# OpticalProbeTest.net
KiCad netlist of a schematic drawn in Altium Designer
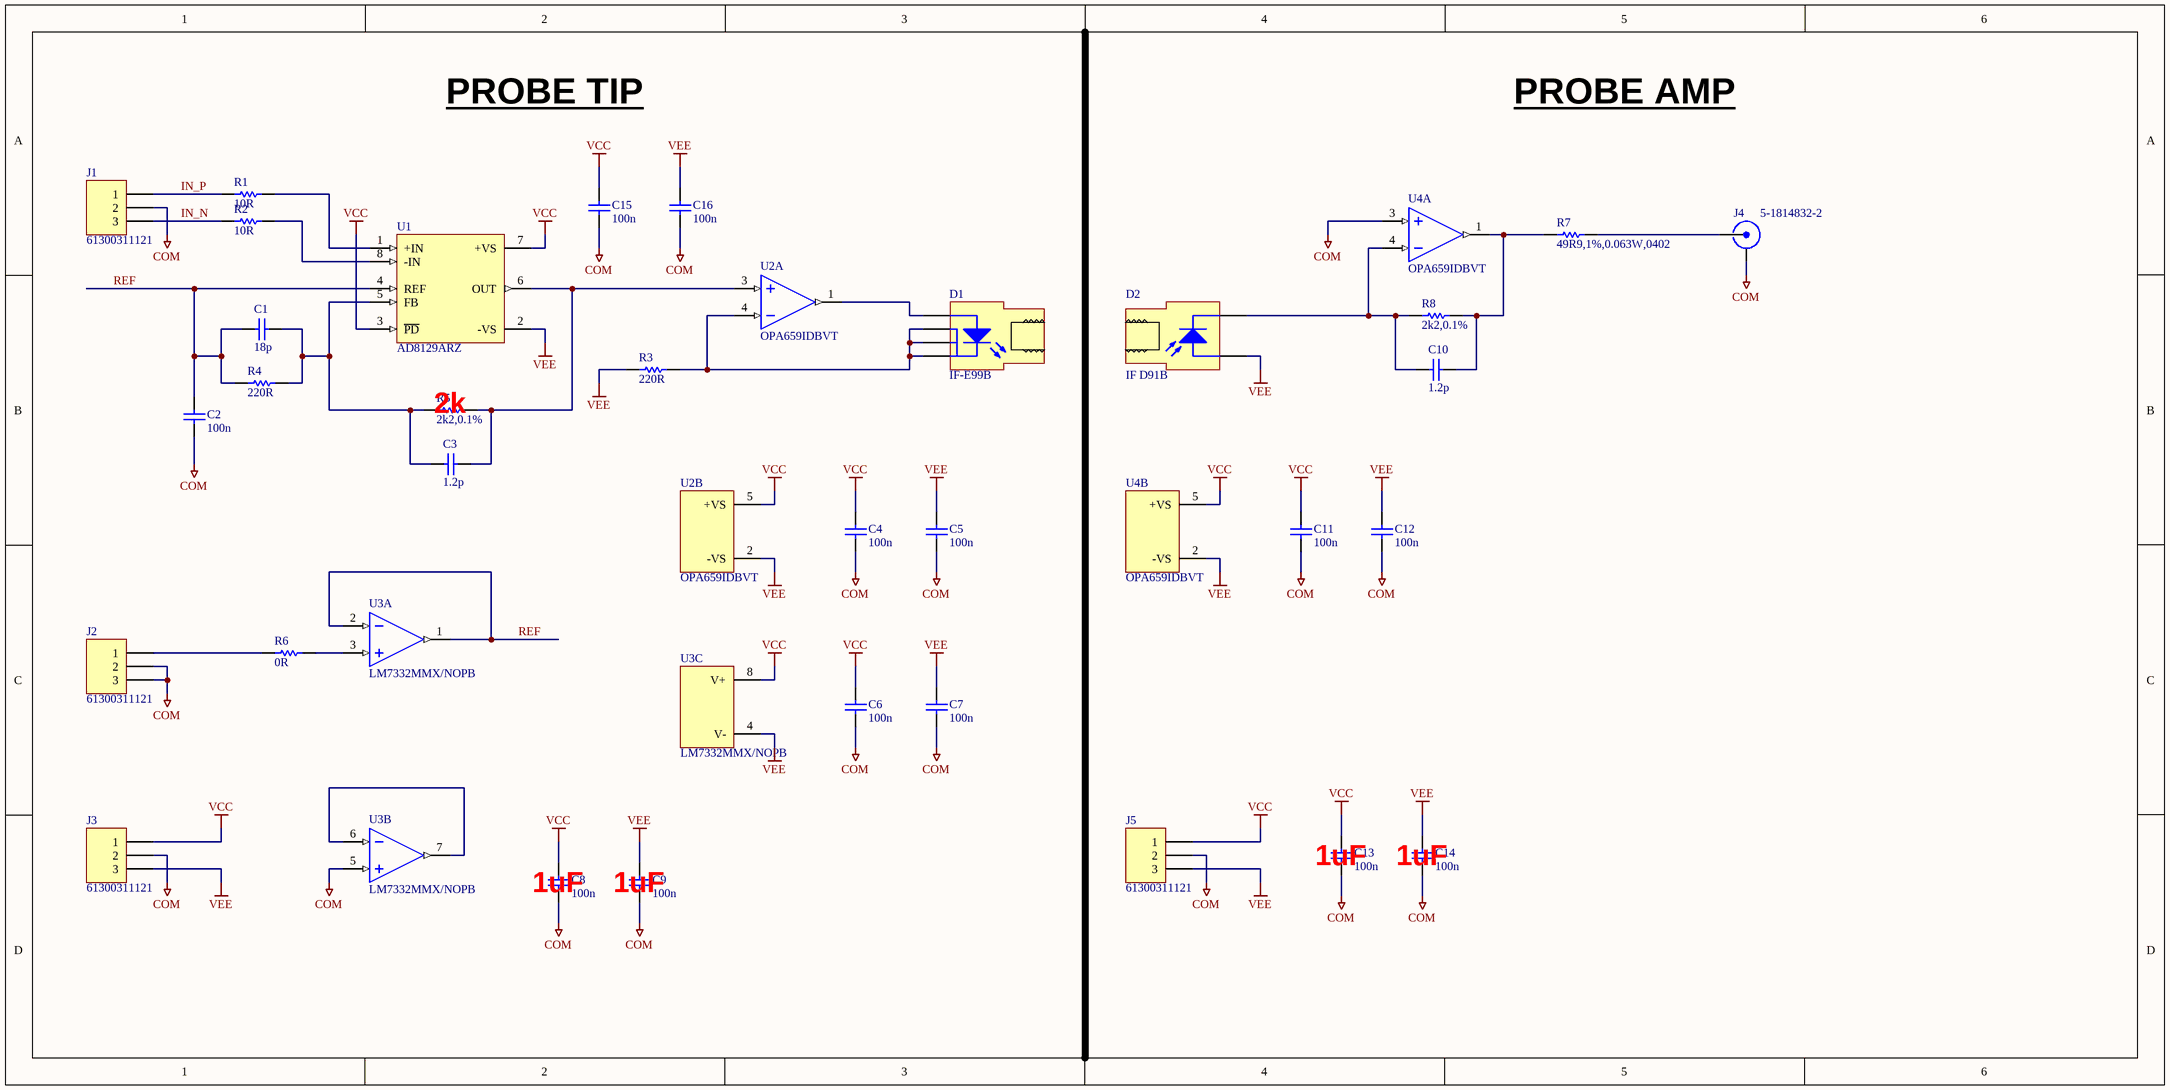
[diagram p0: OpticalProbeTest.SchDoc]

(export (version "E")
  (design (tool "Eeschema 10.0.6"))
  (components
    (comp (ref "C1")
      (value "18p")
      (footprint "CAPC1005X06N")
      (description "18 pF ï¿½5% 25V Ceramic Capacitor C0G, NP0 0402 (1005 Metric)")
      (fields
        (field (name "MANUFACTURER 1 PART NUMBER") "0402N180J250CT")
        (field (name "VENDOR 1 PART NUMBER") "1292-1265-1-ND")
        (field (name "CREATEDBY") "Judd Foster")
      )
      (libsource (lib "Component Library") (part "CAP,Cer,18pF,25VDC,C0G,0402"))
    )
    (comp (ref "C2")
      (value "100n")
      (footprint "CAPC1005X06N")
      (description "0.1ï¿½F ï¿½10% 25V Ceramic Capacitor X7R 0402 (1005 Metric)")
      (fields
        (field (name "MANUFACTURER 1 PART NUMBER") "GRM155R71E104KE14J")
        (field (name "VENDOR 1 PART NUMBER") "490-14603-1-ND")
        (field (name "CREATEDBY") "Judd Foster")
      )
      (libsource (lib "Component Library") (part "CAP,Cer,100nF,25VDC,X7R,0402"))
    )
    (comp (ref "C3")
      (value "1.2p")
      (footprint "CAPC1005X06N")
      (description "1.2 pF ï¿½0.1pF 50V Ceramic Capacitor C0G, NP0 0402 (1005 Metric)")
      (fields
        (field (name "MANUFACTURER 1 PART NUMBER") "GRM1555C1H1R2BA01D")
        (field (name "VENDOR 1 PART NUMBER") "490-6209-1-ND")
        (field (name "CREATEDBY") "Judd Foster")
      )
      (libsource (lib "Component Library") (part "CAP,Cer,1.2pF,50V,C0G,0402"))
    )
    (comp (ref "C4")
      (value "100n")
      (footprint "CAPC1005X06N")
      (description "0.1ï¿½F ï¿½10% 25V Ceramic Capacitor X7R 0402 (1005 Metric)")
      (fields
        (field (name "MANUFACTURER 1 PART NUMBER") "GRM155R71E104KE14J")
        (field (name "VENDOR 1 PART NUMBER") "490-14603-1-ND")
        (field (name "CREATEDBY") "Judd Foster")
      )
      (libsource (lib "Component Library") (part "CAP,Cer,100nF,25VDC,X7R,0402"))
    )
    (comp (ref "C5")
      (value "100n")
      (footprint "CAPC1005X06N")
      (description "0.1ï¿½F ï¿½10% 25V Ceramic Capacitor X7R 0402 (1005 Metric)")
      (fields
        (field (name "MANUFACTURER 1 PART NUMBER") "GRM155R71E104KE14J")
        (field (name "VENDOR 1 PART NUMBER") "490-14603-1-ND")
        (field (name "CREATEDBY") "Judd Foster")
      )
      (libsource (lib "Component Library") (part "CAP,Cer,100nF,25VDC,X7R,0402"))
    )
    (comp (ref "C6")
      (value "100n")
      (footprint "CAPC1005X06N")
      (description "0.1ï¿½F ï¿½10% 25V Ceramic Capacitor X7R 0402 (1005 Metric)")
      (fields
        (field (name "MANUFACTURER 1 PART NUMBER") "GRM155R71E104KE14J")
        (field (name "VENDOR 1 PART NUMBER") "490-14603-1-ND")
        (field (name "CREATEDBY") "Judd Foster")
      )
      (libsource (lib "Component Library") (part "CAP,Cer,100nF,25VDC,X7R,0402"))
    )
    (comp (ref "C7")
      (value "100n")
      (footprint "CAPC1005X06N")
      (description "0.1ï¿½F ï¿½10% 25V Ceramic Capacitor X7R 0402 (1005 Metric)")
      (fields
        (field (name "MANUFACTURER 1 PART NUMBER") "GRM155R71E104KE14J")
        (field (name "VENDOR 1 PART NUMBER") "490-14603-1-ND")
        (field (name "CREATEDBY") "Judd Foster")
      )
      (libsource (lib "Component Library") (part "CAP,Cer,100nF,25VDC,X7R,0402"))
    )
    (comp (ref "C8")
      (value "100n")
      (footprint "CAPC_0805")
      (description "CAP CER 0.1UF 50V X7R 0805")
      (fields
        (field (name "MANUFACTURER 1 PART NUMBER") "C0805C104M5RACTU")
        (field (name "VENDOR 1 PART NUMBER") "399-1169-1-ND")
        (field (name "CREATEDBY") "Judd Foster")
      )
      (libsource (lib "Component Library") (part "CAP,Cer,100nF,50VDC,X7R,0805"))
    )
    (comp (ref "C9")
      (value "100n")
      (footprint "CAPC_0805")
      (description "CAP CER 0.1UF 50V X7R 0805")
      (fields
        (field (name "MANUFACTURER 1 PART NUMBER") "C0805C104M5RACTU")
        (field (name "VENDOR 1 PART NUMBER") "399-1169-1-ND")
        (field (name "CREATEDBY") "Judd Foster")
      )
      (libsource (lib "Component Library") (part "CAP,Cer,100nF,50VDC,X7R,0805"))
    )
    (comp (ref "C10")
      (value "1.2p")
      (footprint "CAPC1005X06N")
      (description "1.2 pF ï¿½0.1pF 50V Ceramic Capacitor C0G, NP0 0402 (1005 Metric)")
      (fields
        (field (name "MANUFACTURER 1 PART NUMBER") "GRM1555C1H1R2BA01D")
        (field (name "VENDOR 1 PART NUMBER") "490-6209-1-ND")
        (field (name "CREATEDBY") "Judd Foster")
      )
      (libsource (lib "Component Library") (part "CAP,Cer,1.2pF,50V,C0G,0402"))
    )
    (comp (ref "C11")
      (value "100n")
      (footprint "CAPC1005X06N")
      (description "0.1ï¿½F ï¿½10% 25V Ceramic Capacitor X7R 0402 (1005 Metric)")
      (fields
        (field (name "MANUFACTURER 1 PART NUMBER") "GRM155R71E104KE14J")
        (field (name "VENDOR 1 PART NUMBER") "490-14603-1-ND")
        (field (name "CREATEDBY") "Judd Foster")
      )
      (libsource (lib "Component Library") (part "CAP,Cer,100nF,25VDC,X7R,0402"))
    )
    (comp (ref "C12")
      (value "100n")
      (footprint "CAPC1005X06N")
      (description "0.1ï¿½F ï¿½10% 25V Ceramic Capacitor X7R 0402 (1005 Metric)")
      (fields
        (field (name "MANUFACTURER 1 PART NUMBER") "GRM155R71E104KE14J")
        (field (name "VENDOR 1 PART NUMBER") "490-14603-1-ND")
        (field (name "CREATEDBY") "Judd Foster")
      )
      (libsource (lib "Component Library") (part "CAP,Cer,100nF,25VDC,X7R,0402"))
    )
    (comp (ref "C13")
      (value "100n")
      (footprint "CAPC_0805")
      (description "CAP CER 0.1UF 50V X7R 0805")
      (fields
        (field (name "MANUFACTURER 1 PART NUMBER") "C0805C104M5RACTU")
        (field (name "VENDOR 1 PART NUMBER") "399-1169-1-ND")
        (field (name "CREATEDBY") "Judd Foster")
      )
      (libsource (lib "Component Library") (part "CAP,Cer,100nF,50VDC,X7R,0805"))
    )
    (comp (ref "C14")
      (value "100n")
      (footprint "CAPC_0805")
      (description "CAP CER 0.1UF 50V X7R 0805")
      (fields
        (field (name "MANUFACTURER 1 PART NUMBER") "C0805C104M5RACTU")
        (field (name "VENDOR 1 PART NUMBER") "399-1169-1-ND")
        (field (name "CREATEDBY") "Judd Foster")
      )
      (libsource (lib "Component Library") (part "CAP,Cer,100nF,50VDC,X7R,0805"))
    )
    (comp (ref "C15")
      (value "100n")
      (footprint "CAPC1005X06N")
      (description "0.1ï¿½F ï¿½10% 25V Ceramic Capacitor X7R 0402 (1005 Metric)")
      (fields
        (field (name "MANUFACTURER 1 PART NUMBER") "GRM155R71E104KE14J")
        (field (name "VENDOR 1 PART NUMBER") "490-14603-1-ND")
        (field (name "CREATEDBY") "Judd Foster")
      )
      (libsource (lib "Component Library") (part "CAP,Cer,100nF,25VDC,X7R,0402"))
    )
    (comp (ref "C16")
      (value "100n")
      (footprint "CAPC1005X06N")
      (description "0.1ï¿½F ï¿½10% 25V Ceramic Capacitor X7R 0402 (1005 Metric)")
      (fields
        (field (name "MANUFACTURER 1 PART NUMBER") "GRM155R71E104KE14J")
        (field (name "VENDOR 1 PART NUMBER") "490-14603-1-ND")
        (field (name "CREATEDBY") "Judd Foster")
      )
      (libsource (lib "Component Library") (part "CAP,Cer,100nF,25VDC,X7R,0402"))
    )
    (comp (ref "D1")
      (value "IF-E99B")
      (footprint "INDUSTRIALFIBEROPTICS_IF-E99B")
      (description "Fiber Optic Transmitter 650nm 1.9V 50 mA Connector-less")
      (fields (field (name "VENDOR 1 PART NUMBER") "FB161-ND") (field (name "CREATEDBY") "Judd Foster"))
      (libsource (lib "Component Library") (part "XMITTER,FIBER OPTIC,650NM,1.9V,IF-E99B"))
    )
    (comp (ref "D2")
      (value "IF D91B")
      (footprint "INDUSTRIALFIBEROPTICS_IF-D91B")
      (description "Fiber Optic Receiver General Purpose 100Mbps")
      (fields (field (name "VENDOR 1 PART NUMBER") "FB200-ND") (field (name "CREATEDBY") "Judd Foster"))
      (libsource (lib "Component Library") (part "RECEIVER,FIBER OPTIC,450-1050NM,IF-D91B"))
    )
    (comp (ref "J1")
      (value "61300311121")
      (footprint "WURTH_61300311121")
      (description "CONN HEADER VERT 3POS 2.54MM")
      (fields (field (name "VENDOR 1 PART NUMBER") "732-5316-ND") (field (name "CREATEDBY") "Judd Foster"))
      (libsource (lib "Component Library") (part "Term,Header,3 Pin,Top,2.54mm"))
    )
    (comp (ref "J2")
      (value "61300311121")
      (footprint "WURTH_61300311121")
      (description "CONN HEADER VERT 3POS 2.54MM")
      (fields (field (name "VENDOR 1 PART NUMBER") "732-5316-ND") (field (name "CREATEDBY") "Judd Foster"))
      (libsource (lib "Component Library") (part "Term,Header,3 Pin,Top,2.54mm"))
    )
    (comp (ref "J3")
      (value "61300311121")
      (footprint "WURTH_61300311121")
      (description "CONN HEADER VERT 3POS 2.54MM")
      (fields (field (name "VENDOR 1 PART NUMBER") "732-5316-ND") (field (name "CREATEDBY") "Judd Foster"))
      (libsource (lib "Component Library") (part "Term,Header,3 Pin,Top,2.54mm"))
    )
    (comp (ref "J4")
      (value "5-1814832-2")
      (footprint "TE_5-1814832-2")
      (description "SMA Connector Jack, Female Socket 50Ohm Through Hole Solder")
      (fields (field (name "VENDOR 1 PART NUMBER") "C482015") (field (name "CREATEDBY") "Judd Foster"))
      (libsource (lib "Component Library") (part "Conn,RF,SMA,Fem,50R,Thru"))
    )
    (comp (ref "J5")
      (value "61300311121")
      (footprint "WURTH_61300311121")
      (description "CONN HEADER VERT 3POS 2.54MM")
      (fields (field (name "VENDOR 1 PART NUMBER") "732-5316-ND") (field (name "CREATEDBY") "Judd Foster"))
      (libsource (lib "Component Library") (part "Term,Header,3 Pin,Top,2.54mm"))
    )
    (comp (ref "R1")
      (value "10R")
      (footprint "RESC1005X04N")
      (description "10 Ohms ï¿½1% 0.063W, 1/16W Chip Resistor 0402 (1005 Metric) Automotive AEC-Q200 Thick Film")
      (fields
        (field (name "MANUFACTURER 1 PART NUMBER") "ERJ-2RKF10R0X")
        (field (name "VENDOR 1 PART NUMBER") "P10.0LCT-ND")
        (field (name "CREATEDBY") "Judd Foster")
      )
      (libsource (lib "Component Library") (part "RES,10R,1%,0.063W,0402"))
    )
    (comp (ref "R2")
      (value "10R")
      (footprint "RESC1005X04N")
      (description "10 Ohms ï¿½1% 0.063W, 1/16W Chip Resistor 0402 (1005 Metric) Automotive AEC-Q200 Thick Film")
      (fields
        (field (name "MANUFACTURER 1 PART NUMBER") "ERJ-2RKF10R0X")
        (field (name "VENDOR 1 PART NUMBER") "P10.0LCT-ND")
        (field (name "CREATEDBY") "Judd Foster")
      )
      (libsource (lib "Component Library") (part "RES,10R,1%,0.063W,0402"))
    )
    (comp (ref "R3")
      (value "220R")
      (footprint "RESC1005X04N")
      (description "220 Ohms ï¿½1% 0.063W, 1/16W Chip Resistor 0402 (1005 Metric) Moisture Resistant Thick Film")
      (fields
        (field (name "MANUFACTURER 1 PART NUMBER") "RC0402FR-07220RL")
        (field (name "VENDOR 1 PART NUMBER") "311-220LRCT-ND")
        (field (name "CREATEDBY") "Judd Foster")
      )
      (libsource (lib "Component Library") (part "RES,220R,1%,0.063W,0402"))
    )
    (comp (ref "R4")
      (value "220R")
      (footprint "RESC1005X04N")
      (description "220 Ohms ï¿½1% 0.063W, 1/16W Chip Resistor 0402 (1005 Metric) Moisture Resistant Thick Film")
      (fields
        (field (name "MANUFACTURER 1 PART NUMBER") "RC0402FR-07220RL")
        (field (name "VENDOR 1 PART NUMBER") "311-220LRCT-ND")
        (field (name "CREATEDBY") "Judd Foster")
      )
      (libsource (lib "Component Library") (part "RES,220R,1%,0.063W,0402"))
    )
    (comp (ref "R5")
      (value "2k2,0.1%")
      (footprint "RESC1005X04N")
      (fields
        (field (name "MANUFACTURER 1 PART NUMBER") "RG1005P-222-B-T5")
        (field (name "VENDOR 1 PART NUMBER") "RG10P2.2KBCT-ND")
        (field (name "CREATEDBY") "Judd Foster")
      )
      (libsource (lib "Component Library") (part "RES,2k2,0.1%,0.063W,0402"))
    )
    (comp (ref "R6")
      (value "0R")
      (footprint "RESC1005X04N")
      (description "0 Ohms Jumper 0.1W, 1/10W Chip Resistor 0402 (1005 Metric) Automotive AEC-Q200 Thick Film")
      (fields
        (field (name "MANUFACTURER 1 PART NUMBER") "ERJ-2GE0R00X")
        (field (name "VENDOR 1 PART NUMBER") "P0.0JCT-ND")
        (field (name "CREATEDBY") "Judd Foster")
      )
      (libsource (lib "Component Library") (part "RES,0R0,0.1W,0402"))
    )
    (comp (ref "R7")
      (value "49R9,1%,0.063W,0402")
      (footprint "RESC1005X04N")
      (description "49.9 Ohms Â±1% 0.063W, 1/16W Chip Resistor 0402 (1005 Metric) Moisture Resistant Thick Film")
      (fields
        (field (name "MANUFACTURER 1 PART NUMBER") "RC0402FR-0749R9L")
        (field (name "VENDOR 1 PART NUMBER") "311-49.9LRCT-ND")
        (field (name "CREATEDBY") "Judd Foster")
      )
      (libsource (lib "Component Library") (part "RES,49R9,1%,0.063W,0402"))
    )
    (comp (ref "R8")
      (value "2k2,0.1%")
      (footprint "RESC1005X04N")
      (fields
        (field (name "MANUFACTURER 1 PART NUMBER") "RG1005P-222-B-T5")
        (field (name "VENDOR 1 PART NUMBER") "RG10P2.2KBCT-ND")
        (field (name "CREATEDBY") "Judd Foster")
      )
      (libsource (lib "Component Library") (part "RES,2k2,0.1%,0.063W,0402"))
    )
    (comp (ref "U1")
      (value "AD8129ARZ")
      (footprint "ANALOGDEVICES_PKG_R-8")
      (description "Differential Amplifier 1 Circuit 8-SOIC")
      (fields
        (field (name "VENDOR 1 PART NUMBER") "505-AD8129ARZ-ND")
        (field (name "CREATEDBY") "Judd Foster")
      )
      (libsource (lib "Component Library") (part "AD8129ARZ"))
    )
    (comp (ref "U2")
      (value "OPA659IDBVT")
      (footprint "TEXASINSTRUMENTS_PKG_DBV0005A")
      (description "J-FET Amplifier 1 Circuit SOT-23-5")
      (fields (field (name "VENDOR 1 PART NUMBER") "296-24971-1-ND") (field (name "CREATEDBY") "Judd Foster"))
      (libsource (lib "Component Library") (part "OPA659IDBVT"))
    )
    (comp (ref "U3")
      (value "LM7332MMX/NOPB")
      (footprint "TEXASINSTRUMENTS_PKG_DGK0008A")
      (description "General Purpose Amplifier 2 Circuit Rail-to-Rail 8-VSSOP")
      (fields
        (field (name "VENDOR 1 PART NUMBER") "296-LM7332MMX/NOPBCT-ND")
        (field (name "CREATEDBY") "Judd Foster")
      )
      (libsource (lib "Component Library") (part "LM7332MMX_NOPB"))
    )
    (comp (ref "U4")
      (value "OPA659IDBVT")
      (footprint "TEXASINSTRUMENTS_PKG_DBV0005A")
      (description "J-FET Amplifier 1 Circuit SOT-23-5")
      (fields (field (name "VENDOR 1 PART NUMBER") "296-24971-1-ND") (field (name "CREATEDBY") "Judd Foster"))
      (libsource (lib "Component Library") (part "OPA659IDBVT"))
    )
  )
  (nets
    (net (code "1") (name "/IN_N") (class "Default")
      (node (ref "J1") (pin "3") (pinfunction "3_3") (pintype "passive"))
      (node (ref "R2") (pin "1") (pinfunction "1_1") (pintype "passive"))
    )
    (net (code "2") (name "/IN_P") (class "Default")
      (node (ref "J1") (pin "1") (pinfunction "1_1") (pintype "passive"))
      (node (ref "R1") (pin "1") (pinfunction "1_1") (pintype "passive"))
    )
    (net (code "3") (name "/REF") (class "Default")
      (node (ref "C1") (pin "1") (pinfunction "1_1") (pintype "passive"))
      (node (ref "C2") (pin "2") (pinfunction "2_2") (pintype "passive"))
      (node (ref "R4") (pin "1") (pinfunction "1_1") (pintype "passive"))
      (node (ref "U1") (pin "4") (pinfunction "REF_4") (pintype "input"))
      (node (ref "U3") (pin "1") (pinfunction "OUTA_1") (pintype "output"))
      (node (ref "U3") (pin "2") (pinfunction "INA-_2") (pintype "input"))
    )
    (net (code "4") (name "COM") (class "Default")
      (node (ref "C11") (pin "1") (pinfunction "1_1") (pintype "passive"))
      (node (ref "C12") (pin "1") (pinfunction "1_1") (pintype "passive"))
      (node (ref "C13") (pin "1") (pinfunction "1_1") (pintype "passive"))
      (node (ref "C14") (pin "1") (pinfunction "1_1") (pintype "passive"))
      (node (ref "C15") (pin "1") (pinfunction "1_1") (pintype "passive"))
      (node (ref "C16") (pin "1") (pinfunction "1_1") (pintype "passive"))
      (node (ref "C2") (pin "1") (pinfunction "1_1") (pintype "passive"))
      (node (ref "C4") (pin "1") (pinfunction "1_1") (pintype "passive"))
      (node (ref "C5") (pin "1") (pinfunction "1_1") (pintype "passive"))
      (node (ref "C6") (pin "1") (pinfunction "1_1") (pintype "passive"))
      (node (ref "C7") (pin "1") (pinfunction "1_1") (pintype "passive"))
      (node (ref "C8") (pin "1") (pinfunction "1_1") (pintype "passive"))
      (node (ref "C9") (pin "1") (pinfunction "1_1") (pintype "passive"))
      (node (ref "J1") (pin "2") (pinfunction "2_2") (pintype "passive"))
      (node (ref "J2") (pin "2") (pinfunction "2_2") (pintype "passive"))
      (node (ref "J2") (pin "3") (pinfunction "3_3") (pintype "passive"))
      (node (ref "J3") (pin "2") (pinfunction "2_2") (pintype "passive"))
      (node (ref "J4") (pin "2") (pinfunction "GND_2") (pintype "passive"))
      (node (ref "J5") (pin "2") (pinfunction "2_2") (pintype "passive"))
      (node (ref "U3") (pin "5") (pinfunction "INB+_5") (pintype "input"))
      (node (ref "U4") (pin "3") (pinfunction "IN+_3") (pintype "input"))
    )
    (net (code "5") (name "Net-(D1-A)") (class "Default")
      (node (ref "D1") (pin "3") (pinfunction "A_3") (pintype "passive"))
      (node (ref "U2") (pin "1") (pinfunction "OUT1_1") (pintype "output"))
    )
    (net (code "6") (name "Net-(D2-K)") (class "Default")
      (node (ref "C10") (pin "2") (pinfunction "2_2") (pintype "passive"))
      (node (ref "D2") (pin "2") (pinfunction "K_2") (pintype "passive"))
      (node (ref "R8") (pin "1") (pinfunction "1_1") (pintype "passive"))
      (node (ref "U4") (pin "4") (pinfunction "IN-_4") (pintype "input"))
    )
    (net (code "7") (name "Net-(J2-Pad1)") (class "Default")
      (node (ref "J2") (pin "1") (pinfunction "1_1") (pintype "passive"))
      (node (ref "R6") (pin "1") (pinfunction "1_1") (pintype "passive"))
    )
    (net (code "8") (name "Net-(J4-RF)") (class "Default")
      (node (ref "J4") (pin "1") (pinfunction "RF_1") (pintype "passive"))
      (node (ref "R7") (pin "2") (pinfunction "2_2") (pintype "passive"))
    )
    (net (code "9") (name "Net-(U1-+IN)") (class "Default")
      (node (ref "R1") (pin "2") (pinfunction "2_2") (pintype "passive"))
      (node (ref "U1") (pin "1") (pinfunction "+IN_1") (pintype "input"))
    )
    (net (code "10") (name "Net-(U1--IN)") (class "Default")
      (node (ref "R2") (pin "2") (pinfunction "2_2") (pintype "passive"))
      (node (ref "U1") (pin "8") (pinfunction "-IN_8") (pintype "input"))
    )
    (net (code "11") (name "Net-(U1-FB)") (class "Default")
      (node (ref "C1") (pin "2") (pinfunction "2_2") (pintype "passive"))
      (node (ref "C3") (pin "2") (pinfunction "2_2") (pintype "passive"))
      (node (ref "R4") (pin "2") (pinfunction "2_2") (pintype "passive"))
      (node (ref "R5") (pin "1") (pinfunction "1_1") (pintype "passive"))
      (node (ref "U1") (pin "5") (pinfunction "FB_5") (pintype "input"))
    )
    (net (code "12") (name "Net-(U1-OUT)") (class "Default")
      (node (ref "C3") (pin "1") (pinfunction "1_1") (pintype "passive"))
      (node (ref "R5") (pin "2") (pinfunction "2_2") (pintype "passive"))
      (node (ref "U1") (pin "6") (pinfunction "OUT_6") (pintype "output"))
      (node (ref "U2") (pin "3") (pinfunction "IN+_3") (pintype "input"))
    )
    (net (code "13") (name "Net-(U2A-IN-)") (class "Default")
      (node (ref "D1") (pin "1") (pinfunction "K_1") (pintype "passive"))
      (node (ref "D1") (pin "2") (pinfunction "K_2") (pintype "passive"))
      (node (ref "D1") (pin "4") (pinfunction "K_4") (pintype "passive"))
      (node (ref "R3") (pin "2") (pinfunction "2_2") (pintype "passive"))
      (node (ref "U2") (pin "4") (pinfunction "IN-_4") (pintype "input"))
    )
    (net (code "14") (name "Net-(U3A-INA+)") (class "Default")
      (node (ref "R6") (pin "2") (pinfunction "2_2") (pintype "passive"))
      (node (ref "U3") (pin "3") (pinfunction "INA+_3") (pintype "input"))
    )
    (net (code "15") (name "Net-(U3B-INB-)") (class "Default")
      (node (ref "U3") (pin "6") (pinfunction "INB-_6") (pintype "input"))
      (node (ref "U3") (pin "7") (pinfunction "OUTB_7") (pintype "output"))
    )
    (net (code "16") (name "Net-(U4A-OUT1)") (class "Default")
      (node (ref "C10") (pin "1") (pinfunction "1_1") (pintype "passive"))
      (node (ref "R7") (pin "1") (pinfunction "1_1") (pintype "passive"))
      (node (ref "R8") (pin "2") (pinfunction "2_2") (pintype "passive"))
      (node (ref "U4") (pin "1") (pinfunction "OUT1_1") (pintype "output"))
    )
    (net (code "17") (name "VCC") (class "Default")
      (node (ref "C11") (pin "2") (pinfunction "2_2") (pintype "passive"))
      (node (ref "C13") (pin "2") (pinfunction "2_2") (pintype "passive"))
      (node (ref "C15") (pin "2") (pinfunction "2_2") (pintype "passive"))
      (node (ref "C4") (pin "2") (pinfunction "2_2") (pintype "passive"))
      (node (ref "C6") (pin "2") (pinfunction "2_2") (pintype "passive"))
      (node (ref "C8") (pin "2") (pinfunction "2_2") (pintype "passive"))
      (node (ref "J3") (pin "1") (pinfunction "1_1") (pintype "passive"))
      (node (ref "J5") (pin "1") (pinfunction "1_1") (pintype "passive"))
      (node (ref "U1") (pin "3") (pinfunction "~{PD}_3") (pintype "input"))
      (node (ref "U1") (pin "7") (pinfunction "+VS_7") (pintype "power_in"))
      (node (ref "U2") (pin "5") (pinfunction "+VS_5") (pintype "power_in"))
      (node (ref "U3") (pin "8") (pinfunction "V+_8") (pintype "power_in"))
      (node (ref "U4") (pin "5") (pinfunction "+VS_5") (pintype "power_in"))
    )
    (net (code "18") (name "VEE") (class "Default")
      (node (ref "C12") (pin "2") (pinfunction "2_2") (pintype "passive"))
      (node (ref "C14") (pin "2") (pinfunction "2_2") (pintype "passive"))
      (node (ref "C16") (pin "2") (pinfunction "2_2") (pintype "passive"))
      (node (ref "C5") (pin "2") (pinfunction "2_2") (pintype "passive"))
      (node (ref "C7") (pin "2") (pinfunction "2_2") (pintype "passive"))
      (node (ref "C9") (pin "2") (pinfunction "2_2") (pintype "passive"))
      (node (ref "D2") (pin "1") (pinfunction "A_1") (pintype "passive"))
      (node (ref "J3") (pin "3") (pinfunction "3_3") (pintype "passive"))
      (node (ref "J5") (pin "3") (pinfunction "3_3") (pintype "passive"))
      (node (ref "R3") (pin "1") (pinfunction "1_1") (pintype "passive"))
      (node (ref "U1") (pin "2") (pinfunction "-VS_2") (pintype "power_in"))
      (node (ref "U2") (pin "2") (pinfunction "-VS_2") (pintype "power_in"))
      (node (ref "U3") (pin "4") (pinfunction "V-_4") (pintype "power_in"))
      (node (ref "U4") (pin "2") (pinfunction "-VS_2") (pintype "power_in"))
    )
  )
)
